# 02_Seven_Segment.net
KiCad netlist of a schematic drawn in Altium Designer
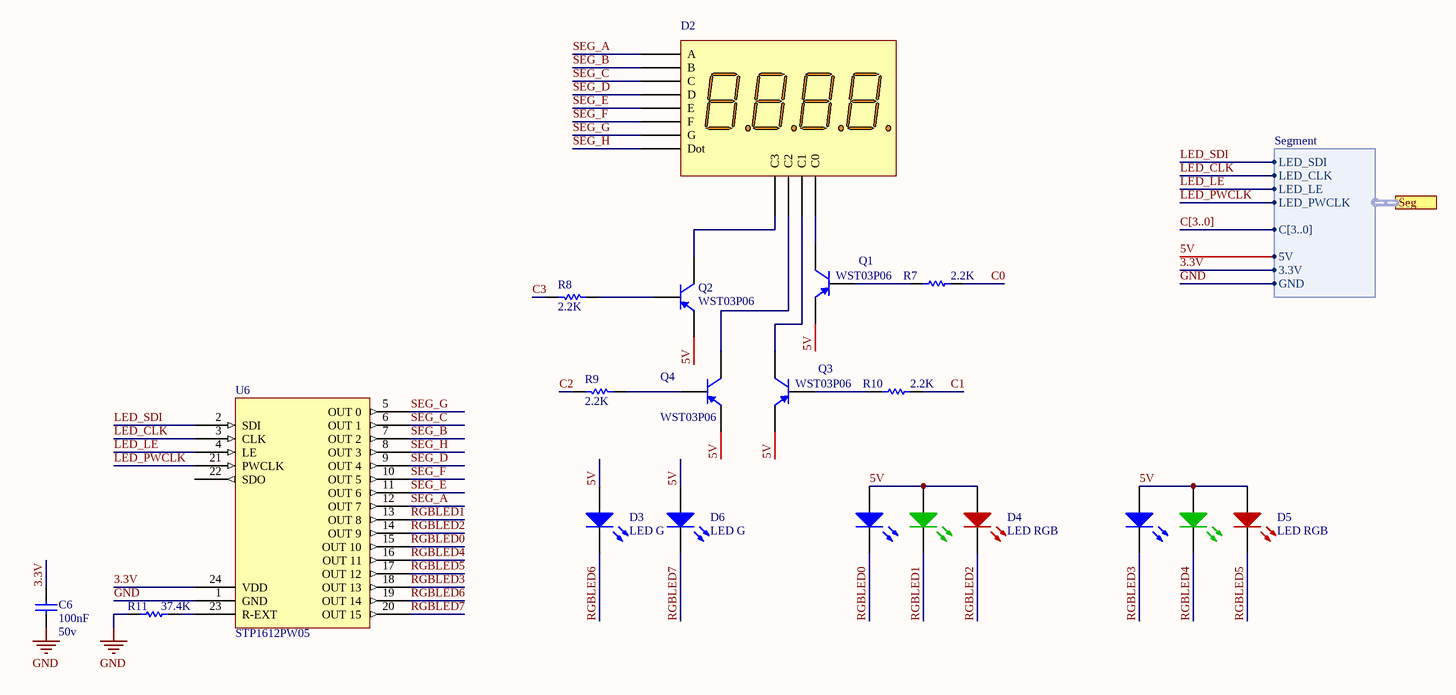
[diagram p0: [02] Seven Segment.SchDoc]

(export (version "E")
  (design (tool "Eeschema 10.0.6"))
  (components
    (comp (ref "C6")
      (value "100nF")
      (footprint "MY_0603")
      (description "None polar capacitor")
      (fields (field (name "ASID PART NUMBER") "C-AS") (field (name "VOLTE") "50v"))
      (libsource (lib "Mylib Rev 4") (part "Cap ceramic"))
    )
    (comp (ref "D2")
      (value "comon anode 4x7 segment")
      (footprint "MY_4X7_seg")
      (fields (field (name "ASID PART NUMBER") "-AS"))
      (libsource (lib "Mylib Rev 4") (part "4x7 segment"))
    )
    (comp (ref "D3")
      (value "LED G")
      (footprint "MY_LED_0805")
      (description "Typical INFRARED GaAs LED")
      (fields (field (name "ASID PART NUMBER") "LED-AS"))
      (libsource (lib "Mylib Rev 4") (part "LED"))
    )
    (comp (ref "D4")
      (value "LED RGB")
      (footprint "MY_RGB5050")
      (description "Enhanced Power RGB LED")
      (fields (field (name "ASID PART NUMBER") "RGB LED"))
      (libsource (lib "Mylib Rev 4") (part "LED RGB"))
    )
    (comp (ref "D5")
      (value "LED RGB")
      (footprint "MY_RGB5050")
      (description "Enhanced Power RGB LED")
      (fields (field (name "ASID PART NUMBER") "RGB LED"))
      (libsource (lib "Mylib Rev 4") (part "LED RGB"))
    )
    (comp (ref "D6")
      (value "LED G")
      (footprint "MY_LED_0805")
      (description "Typical INFRARED GaAs LED")
      (fields (field (name "ASID PART NUMBER") "LED-AS"))
      (libsource (lib "Mylib Rev 4") (part "LED"))
    )
    (comp (ref "Q1")
      (value "WST03P06")
      (footprint "SOT-23A_N")
      (description "PNP General Purpose Amplifier")
      (fields (field (name "PUBLISHER") "Altium Limited"))
      (libsource (lib "FSC Discrete BJT") (part "BC807-16"))
    )
    (comp (ref "Q2")
      (value "WST03P06")
      (footprint "SOT-23A_N")
      (description "PNP General Purpose Amplifier")
      (fields (field (name "PUBLISHER") "Altium Limited"))
      (libsource (lib "FSC Discrete BJT") (part "BC807-16"))
    )
    (comp (ref "Q3")
      (value "WST03P06")
      (footprint "SOT-23A_N")
      (description "PNP General Purpose Amplifier")
      (fields (field (name "PUBLISHER") "Altium Limited"))
      (libsource (lib "FSC Discrete BJT") (part "BC807-16"))
    )
    (comp (ref "Q4")
      (value "WST03P06")
      (footprint "SOT-23A_N")
      (description "PNP General Purpose Amplifier")
      (fields (field (name "PUBLISHER") "Altium Limited"))
      (libsource (lib "FSC Discrete BJT") (part "BC807-16"))
    )
    (comp (ref "R7")
      (value "2.2K")
      (footprint "MY_0805")
      (description "Standard resistor")
      (fields (field (name "ASID PART NUMBER") "Res-AS"))
      (libsource (lib "Mylib Rev 4") (part "Res"))
    )
    (comp (ref "R8")
      (value "2.2K")
      (footprint "MY_0805")
      (description "Standard resistor")
      (fields (field (name "ASID PART NUMBER") "Res-AS"))
      (libsource (lib "Mylib Rev 4") (part "Res"))
    )
    (comp (ref "R9")
      (value "2.2K")
      (footprint "MY_0805")
      (description "Standard resistor")
      (fields (field (name "ASID PART NUMBER") "Res-AS"))
      (libsource (lib "Mylib Rev 4") (part "Res"))
    )
    (comp (ref "R10")
      (value "2.2K")
      (footprint "MY_0805")
      (description "Standard resistor")
      (fields (field (name "ASID PART NUMBER") "Res-AS"))
      (libsource (lib "Mylib Rev 4") (part "Res"))
    )
    (comp (ref "R11")
      (value "37.4K")
      (footprint "MY_0603")
      (description "Standard resistor")
      (fields (field (name "ASID PART NUMBER") "Res-AS"))
      (libsource (lib "Mylib Rev 4") (part "Res"))
    )
    (comp (ref "U6")
      (value "STP1612PW05")
      (footprint "MY_SOIC24")
      (description "16-channel LED driver with 16-bit PWM")
      (libsource (lib "Mylib Rev 4") (part "STP1612PW05"))
    )
  )
  (nets
    (net (code "2") (name "/3.3V") (class "Default")
      (node (ref "C6") (pin "2") (pinfunction "2_2") (pintype "passive"))
      (node (ref "U6") (pin "24") (pinfunction "VDD_24") (pintype "power_in"))
    )
    (net (code "3") (name "/5V") (class "Default")
      (node (ref "D3") (pin "A") (pinfunction "A_A") (pintype "passive"))
      (node (ref "D4") (pin "AB") (pinfunction "A_AB") (pintype "passive"))
      (node (ref "D4") (pin "AG") (pinfunction "A_AG") (pintype "passive"))
      (node (ref "D4") (pin "AR") (pinfunction "A_AR") (pintype "passive"))
      (node (ref "D5") (pin "AB") (pinfunction "A_AB") (pintype "passive"))
      (node (ref "D5") (pin "AG") (pinfunction "A_AG") (pintype "passive"))
      (node (ref "D5") (pin "AR") (pinfunction "A_AR") (pintype "passive"))
      (node (ref "D6") (pin "A") (pinfunction "A_A") (pintype "passive"))
      (node (ref "Q1") (pin "2") (pinfunction "E_2") (pintype "passive"))
      (node (ref "Q2") (pin "2") (pinfunction "E_2") (pintype "passive"))
      (node (ref "Q3") (pin "2") (pinfunction "E_2") (pintype "passive"))
      (node (ref "Q4") (pin "2") (pinfunction "E_2") (pintype "passive"))
    )
    (net (code "4") (name "/C0") (class "Default")
      (node (ref "R7") (pin "2") (pinfunction "2_2") (pintype "passive"))
    )
    (net (code "5") (name "/C1") (class "Default")
      (node (ref "R10") (pin "2") (pinfunction "2_2") (pintype "passive"))
    )
    (net (code "6") (name "/C2") (class "Default")
      (node (ref "R9") (pin "2") (pinfunction "2_2") (pintype "passive"))
    )
    (net (code "7") (name "/C3") (class "Default")
      (node (ref "R8") (pin "2") (pinfunction "2_2") (pintype "passive"))
    )
    (net (code "9") (name "/LED_CLK") (class "Default")
      (node (ref "U6") (pin "3") (pinfunction "CLK_3") (pintype "input"))
    )
    (net (code "10") (name "/LED_LE") (class "Default")
      (node (ref "U6") (pin "4") (pinfunction "LE_4") (pintype "input"))
    )
    (net (code "11") (name "/LED_PWCLK") (class "Default")
      (node (ref "U6") (pin "21") (pinfunction "PWCLK_21") (pintype "input"))
    )
    (net (code "12") (name "/LED_SDI") (class "Default")
      (node (ref "U6") (pin "2") (pinfunction "SDI_2") (pintype "input"))
    )
    (net (code "13") (name "/RGBLED0") (class "Default")
      (node (ref "D4") (pin "KB") (pinfunction "K_KB") (pintype "passive"))
      (node (ref "U6") (pin "15") (pinfunction "OUT_10_15") (pintype "output"))
    )
    (net (code "14") (name "/RGBLED1") (class "Default")
      (node (ref "D4") (pin "KG") (pinfunction "K_KG") (pintype "passive"))
      (node (ref "U6") (pin "13") (pinfunction "OUT_8_13") (pintype "output"))
    )
    (net (code "15") (name "/RGBLED2") (class "Default")
      (node (ref "D4") (pin "KR") (pinfunction "K_KR") (pintype "passive"))
      (node (ref "U6") (pin "14") (pinfunction "OUT_9_14") (pintype "output"))
    )
    (net (code "16") (name "/RGBLED3") (class "Default")
      (node (ref "D5") (pin "KB") (pinfunction "K_KB") (pintype "passive"))
      (node (ref "U6") (pin "18") (pinfunction "OUT_13_18") (pintype "output"))
    )
    (net (code "17") (name "/RGBLED4") (class "Default")
      (node (ref "D5") (pin "KG") (pinfunction "K_KG") (pintype "passive"))
      (node (ref "U6") (pin "16") (pinfunction "OUT_11_16") (pintype "output"))
    )
    (net (code "18") (name "/RGBLED5") (class "Default")
      (node (ref "D5") (pin "KR") (pinfunction "K_KR") (pintype "passive"))
      (node (ref "U6") (pin "17") (pinfunction "OUT_12_17") (pintype "output"))
    )
    (net (code "19") (name "/RGBLED6") (class "Default")
      (node (ref "D3") (pin "K") (pinfunction "K_K") (pintype "passive"))
      (node (ref "U6") (pin "19") (pinfunction "OUT_14_19") (pintype "output"))
    )
    (net (code "20") (name "/RGBLED7") (class "Default")
      (node (ref "D6") (pin "K") (pinfunction "K_K") (pintype "passive"))
      (node (ref "U6") (pin "20") (pinfunction "OUT_15_20") (pintype "output"))
    )
    (net (code "21") (name "/SEG_A") (class "Default")
      (node (ref "D2") (pin "11") (pinfunction "A_11") (pintype "passive"))
      (node (ref "U6") (pin "12") (pinfunction "OUT_7_12") (pintype "output"))
    )
    (net (code "22") (name "/SEG_B") (class "Default")
      (node (ref "D2") (pin "7") (pinfunction "B_7") (pintype "passive"))
      (node (ref "U6") (pin "7") (pinfunction "OUT_2_7") (pintype "output"))
    )
    (net (code "23") (name "/SEG_C") (class "Default")
      (node (ref "D2") (pin "4") (pinfunction "C_4") (pintype "passive"))
      (node (ref "U6") (pin "6") (pinfunction "OUT_1_6") (pintype "output"))
    )
    (net (code "24") (name "/SEG_D") (class "Default")
      (node (ref "D2") (pin "2") (pinfunction "D_2") (pintype "passive"))
      (node (ref "U6") (pin "9") (pinfunction "OUT_4_9") (pintype "output"))
    )
    (net (code "25") (name "/SEG_E") (class "Default")
      (node (ref "D2") (pin "1") (pinfunction "E_1") (pintype "passive"))
      (node (ref "U6") (pin "11") (pinfunction "OUT_6_11") (pintype "output"))
    )
    (net (code "26") (name "/SEG_F") (class "Default")
      (node (ref "D2") (pin "10") (pinfunction "F_10") (pintype "passive"))
      (node (ref "U6") (pin "10") (pinfunction "OUT_5_10") (pintype "output"))
    )
    (net (code "27") (name "/SEG_G") (class "Default")
      (node (ref "D2") (pin "5") (pinfunction "G_5") (pintype "passive"))
      (node (ref "U6") (pin "5") (pinfunction "OUT_0_5") (pintype "output"))
    )
    (net (code "28") (name "/SEG_H") (class "Default")
      (node (ref "D2") (pin "3") (pinfunction "Dot_3") (pintype "passive"))
      (node (ref "U6") (pin "8") (pinfunction "OUT_3_8") (pintype "output"))
    )
    (net (code "30") (name "GND") (class "Default")
      (node (ref "C6") (pin "1") (pinfunction "1_1") (pintype "passive"))
      (node (ref "R11") (pin "1") (pinfunction "1_1") (pintype "passive"))
      (node (ref "U6") (pin "1") (pinfunction "GND_1") (pintype "power_in"))
    )
    (net (code "31") (name "Net-(D2-C0)") (class "Default")
      (node (ref "D2") (pin "12") (pinfunction "C0_12") (pintype "passive"))
      (node (ref "Q1") (pin "3") (pinfunction "C_3") (pintype "passive"))
    )
    (net (code "32") (name "Net-(D2-C1)") (class "Default")
      (node (ref "D2") (pin "9") (pinfunction "C1_9") (pintype "passive"))
      (node (ref "Q3") (pin "3") (pinfunction "C_3") (pintype "passive"))
    )
    (net (code "33") (name "Net-(D2-C2)") (class "Default")
      (node (ref "D2") (pin "8") (pinfunction "C2_8") (pintype "passive"))
      (node (ref "Q4") (pin "3") (pinfunction "C_3") (pintype "passive"))
    )
    (net (code "34") (name "Net-(D2-C3)") (class "Default")
      (node (ref "D2") (pin "6") (pinfunction "C3_6") (pintype "passive"))
      (node (ref "Q2") (pin "3") (pinfunction "C_3") (pintype "passive"))
    )
    (net (code "35") (name "Net-(Q1-B)") (class "Default")
      (node (ref "Q1") (pin "1") (pinfunction "B_1") (pintype "passive"))
      (node (ref "R7") (pin "1") (pinfunction "1_1") (pintype "passive"))
    )
    (net (code "36") (name "Net-(Q2-B)") (class "Default")
      (node (ref "Q2") (pin "1") (pinfunction "B_1") (pintype "passive"))
      (node (ref "R8") (pin "1") (pinfunction "1_1") (pintype "passive"))
    )
    (net (code "37") (name "Net-(Q3-B)") (class "Default")
      (node (ref "Q3") (pin "1") (pinfunction "B_1") (pintype "passive"))
      (node (ref "R10") (pin "1") (pinfunction "1_1") (pintype "passive"))
    )
    (net (code "38") (name "Net-(Q4-B)") (class "Default")
      (node (ref "Q4") (pin "1") (pinfunction "B_1") (pintype "passive"))
      (node (ref "R9") (pin "1") (pinfunction "1_1") (pintype "passive"))
    )
    (net (code "39") (name "Net-(U6-R-EXT)") (class "Default")
      (node (ref "R11") (pin "2") (pinfunction "2_2") (pintype "passive"))
      (node (ref "U6") (pin "23") (pinfunction "R-EXT_23") (pintype "passive"))
    )
    (net (code "40") (name "unconnected-(U6-SDO-Pad22)") (class "Default")
      (node (ref "U6") (pin "22") (pinfunction "SDO_22") (pintype "output"))
    )
  )
)
